# QCLogic_Rev_A_Sht7_MCU_CTRL.net
KiCad netlist of a schematic drawn in Altium Designer
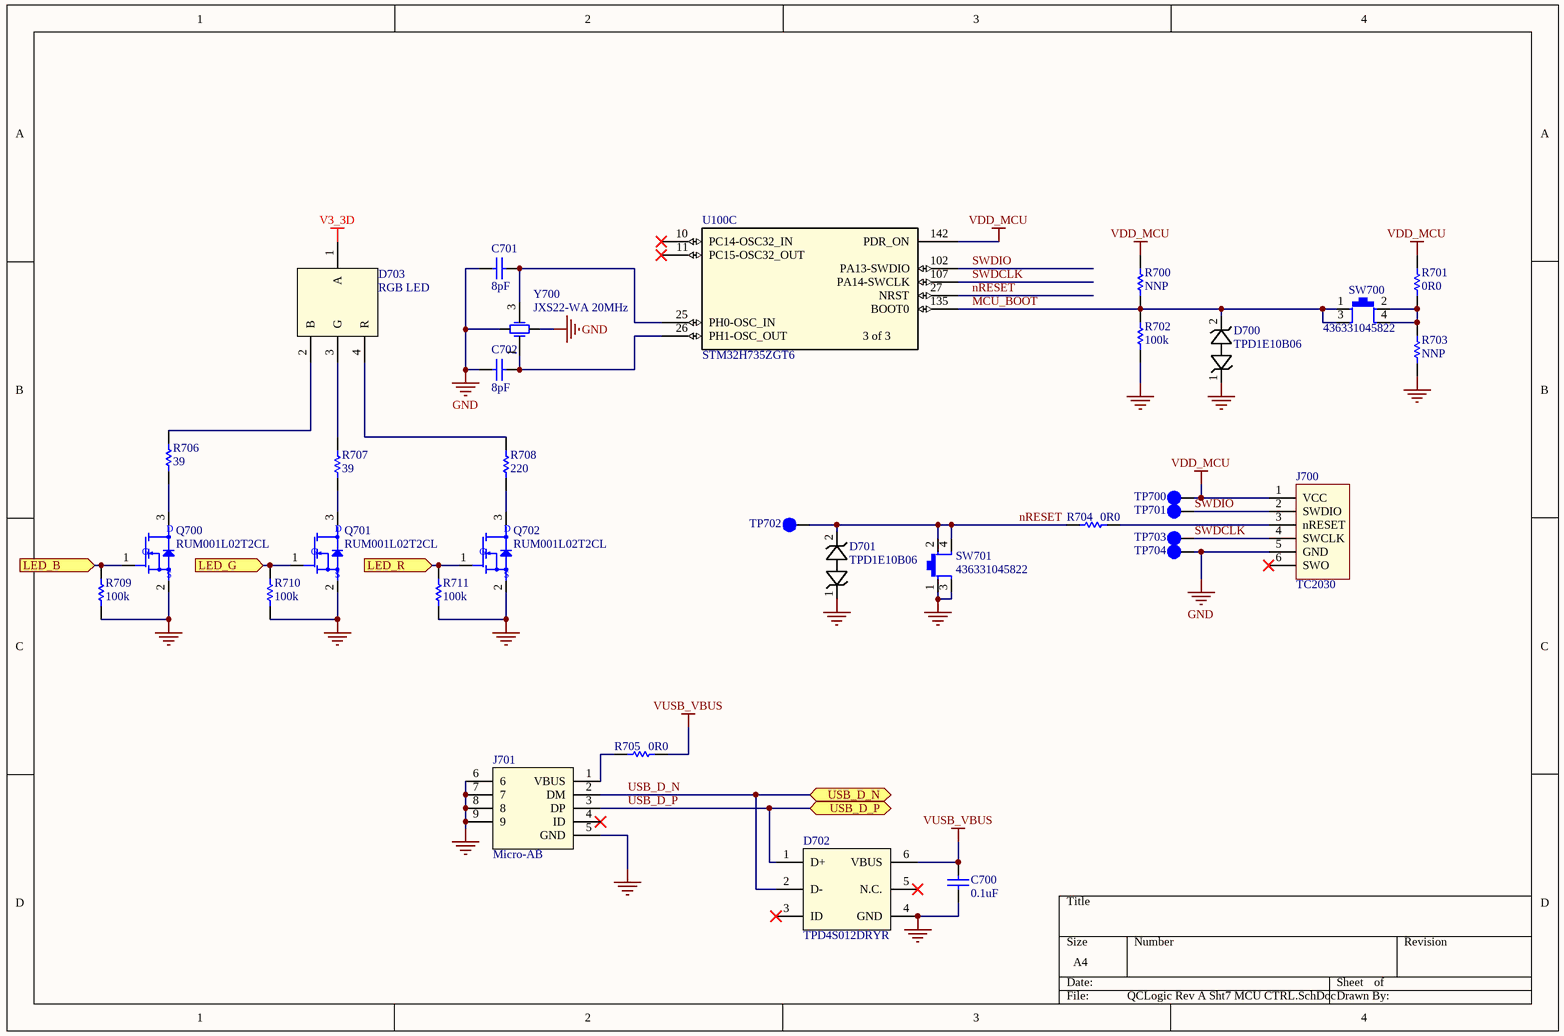
[diagram p0: QCLogic Rev A Sht7 MCU CTRL.SchDoc]

(export (version "E")
  (design (tool "Eeschema 10.0.6"))
  (components
    (comp (ref "C700")
      (value "0.1uF")
      (footprint "SMD CAP 0402")
      (description "CAP CER 0.1UF 25V X7R 0402")
      (fields (field (name "2. MANUFACTURER PART NUMBER") "CC0402KRX7R8BB104"))
      (libsource (lib "SBCLib") (part "CAP MLCC SMD"))
    )
    (comp (ref "C701")
      (value "8pF")
      (footprint "SMD CAP 0402")
      (description "CAP CER 8PF 50V C0G/NP0 0402")
      (fields (field (name "2. MANUFACTURER PART NUMBER") "CL05C080CB5NNNC"))
      (libsource (lib "SBCLib") (part "CAP MLCC SMD"))
    )
    (comp (ref "C702")
      (value "8pF")
      (footprint "SMD CAP 0402")
      (description "CAP CER 8PF 50V C0G/NP0 0402")
      (fields (field (name "2. MANUFACTURER PART NUMBER") "CL05C080CB5NNNC"))
      (libsource (lib "SBCLib") (part "CAP MLCC SMD"))
    )
    (comp (ref "D700")
      (value "TPD1E10B06")
      (footprint "DIODE 0402 2-X1SON")
      (description "DIODE TVS DIODE 5.5V 14V 2X1SON")
      (fields (field (name "2. MANUFACTURER PART NUMBER") "TPD1E10B06DPYR"))
      (libsource (lib "SBCLib") (part "DIODE TVS DIODE 5.5V 14V 2X1SON"))
    )
    (comp (ref "D701")
      (value "TPD1E10B06")
      (footprint "DIODE 0402 2-X1SON")
      (description "DIODE TVS DIODE 5.5V 14V 2X1SON")
      (fields (field (name "2. MANUFACTURER PART NUMBER") "TPD1E10B06DPYR"))
      (libsource (lib "SBCLib") (part "DIODE TVS DIODE 5.5V 14V 2X1SON"))
    )
    (comp (ref "D702")
      (value "TPD4S012DRYR")
      (footprint "SON-6 1.45x1")
      (description "DIODE TVS 4CH 5.5V 6SON")
      (libsource (lib "SBCLib") (part "DIODE TVS 4CH 5.5V 6SON"))
    )
    (comp (ref "D703")
      (value "RGB LED")
      (footprint "PLCC-4 LED ASMB-MTB0-0A3A2")
      (description "LED RGB DIFFUSED 4PLCC SMD")
      (fields (field (name "2. MANUFACTURER PART NUMBER") "ASMB-MTB0-0A3A2"))
      (libsource (lib "SBCLib") (part "LED RGB DIFFUSED 4PLCC SMD"))
    )
    (comp (ref "J700")
      (value "TC2030")
      (footprint "tag-connect-6")
      (description "TC2030 PGM PADS")
      (fields (field (name "2. MANUFACTURER PART NUMBER") "NA"))
      (libsource (lib "MasterLiiiib") (part "TC2030"))
    )
    (comp (ref "J701")
      (value "Micro-AB")
      (footprint "CONN USB MICRO_AB")
      (description "CONN RCPT USB2.0 MICRO AB SMD RA")
      (fields (field (name "2. MANUFACTURER PART NUMBER") "ZX62-AB-5PA(31)"))
      (libsource (lib "SBCLib") (part "CONN RCPT USB2.0 MICRO AB SMD RA"))
    )
    (comp (ref "Q700")
      (value "RUM001L02T2CL")
      (footprint "SOT-723")
      (description "TRANS FET N-CH 20V 0.1A SOT-723 RUM001L02T2CL")
      (libsource (lib "SBCLib") (part "TRANS FET N-CH 20V 0.1A SOT-723 RUM001L02T2CL"))
    )
    (comp (ref "Q701")
      (value "RUM001L02T2CL")
      (footprint "SOT-723")
      (description "TRANS FET N-CH 20V 0.1A SOT-723 RUM001L02T2CL")
      (libsource (lib "SBCLib") (part "TRANS FET N-CH 20V 0.1A SOT-723 RUM001L02T2CL"))
    )
    (comp (ref "Q702")
      (value "RUM001L02T2CL")
      (footprint "SOT-723")
      (description "TRANS FET N-CH 20V 0.1A SOT-723 RUM001L02T2CL")
      (libsource (lib "SBCLib") (part "TRANS FET N-CH 20V 0.1A SOT-723 RUM001L02T2CL"))
    )
    (comp (ref "R700")
      (value "NNP")
      (footprint "SMD RES 0402")
      (description "RES SMD 100K OHM 1% 1/16W 0402")
      (fields (field (name "2. MANUFACTURER PART NUMBER") "RC0402FR-07100KL"))
      (libsource (lib "SBCLib") (part "RES SMD"))
    )
    (comp (ref "R701")
      (value "0R0")
      (footprint "SMD RES 0402")
      (description "RES SMD 0 OHM JUMPER 1/16W 0402")
      (fields (field (name "2. MANUFACTURER PART NUMBER") "RC0402FR-070RL"))
      (libsource (lib "SBCLib") (part "RES SMD"))
    )
    (comp (ref "R702")
      (value "100k")
      (footprint "SMD RES 0402")
      (description "RES SMD 100K OHM 1% 1/16W 0402")
      (fields (field (name "2. MANUFACTURER PART NUMBER") "RC0402FR-07100KL"))
      (libsource (lib "SBCLib") (part "RES SMD"))
    )
    (comp (ref "R703")
      (value "NNP")
      (footprint "SMD RES 0402")
      (description "RES SMD 0 OHM JUMPER 1/16W 0402")
      (fields (field (name "2. MANUFACTURER PART NUMBER") "RC0402FR-070RL"))
      (libsource (lib "SBCLib") (part "RES SMD"))
    )
    (comp (ref "R704")
      (value "0R0")
      (footprint "SMD RES 0402")
      (description "RES SMD 0 OHM JUMPER 1/16W 0402")
      (fields (field (name "2. MANUFACTURER PART NUMBER") "RC0402FR-070RL"))
      (libsource (lib "SBCLib") (part "RES SMD"))
    )
    (comp (ref "R705")
      (value "0R0")
      (footprint "SMD RES 0402")
      (description "RES SMD 0 OHM JUMPER 1/16W 0402")
      (fields (field (name "2. MANUFACTURER PART NUMBER") "RC0402FR-070RL"))
      (libsource (lib "SBCLib") (part "RES SMD"))
    )
    (comp (ref "R706")
      (value "39")
      (footprint "SMD RES 0402")
      (description "RES SMD 39 OHM 5% 1/16W 0402")
      (fields (field (name "2. MANUFACTURER PART NUMBER") "RC0402JR-0739RL"))
      (libsource (lib "SBCLib") (part "RES SMD"))
    )
    (comp (ref "R707")
      (value "39")
      (footprint "SMD RES 0402")
      (description "RES SMD 39 OHM 5% 1/16W 0402")
      (fields (field (name "2. MANUFACTURER PART NUMBER") "RC0402JR-0739RL"))
      (libsource (lib "SBCLib") (part "RES SMD"))
    )
    (comp (ref "R708")
      (value "220")
      (footprint "SMD RES 0402")
      (description "RES SMD 220 OHM 5% 1/16W 0402")
      (fields (field (name "2. MANUFACTURER PART NUMBER") "RC0402JR-07220RL"))
      (libsource (lib "SBCLib") (part "RES SMD"))
    )
    (comp (ref "R709")
      (value "100k")
      (footprint "SMD RES 0402")
      (description "RES SMD 100K OHM 1% 1/16W 0402")
      (fields (field (name "2. MANUFACTURER PART NUMBER") "RC0402FR-07100KL"))
      (libsource (lib "SBCLib") (part "RES SMD"))
    )
    (comp (ref "R710")
      (value "100k")
      (footprint "SMD RES 0402")
      (description "RES SMD 100K OHM 1% 1/16W 0402")
      (fields (field (name "2. MANUFACTURER PART NUMBER") "RC0402FR-07100KL"))
      (libsource (lib "SBCLib") (part "RES SMD"))
    )
    (comp (ref "R711")
      (value "100k")
      (footprint "SMD RES 0402")
      (description "RES SMD 100K OHM 1% 1/16W 0402")
      (fields (field (name "2. MANUFACTURER PART NUMBER") "RC0402FR-07100KL"))
      (libsource (lib "SBCLib") (part "RES SMD"))
    )
    (comp (ref "SW700")
      (value "436331045822")
      (footprint "BUTTON 436331045822")
      (description "SWITCH R/A TACTILE SPST-NO 0.05A 12V")
      (libsource (lib "") (part "SWITCH R/A TACTILE SPST-NO 0.05A 12V_1"))
    )
    (comp (ref "SW701")
      (value "436331045822")
      (footprint "BUTTON 436331045822")
      (description "SWITCH R/A TACTILE SPST-NO 0.05A 12V")
      (libsource (lib "SBCLib") (part "SWITCH R/A TACTILE SPST-NO 0.05A 12V"))
    )
    (comp (ref "TP700")
      (value "TESTPOINT SMD")
      (footprint "TESTPOINT 1mm DIA")
      (description "TESTPOINT SMD PAD")
      (libsource (lib "SBCLib") (part "TESTPOINT PAD"))
    )
    (comp (ref "TP701")
      (value "TESTPOINT SMD")
      (footprint "TESTPOINT 1mm DIA")
      (description "TESTPOINT SMD PAD")
      (libsource (lib "SBCLib") (part "TESTPOINT PAD"))
    )
    (comp (ref "TP702")
      (value "TESTPOINT SMD")
      (footprint "TESTPOINT 1mm DIA")
      (description "TESTPOINT SMD PAD")
      (libsource (lib "SBCLib") (part "TESTPOINT PAD"))
    )
    (comp (ref "TP703")
      (value "TESTPOINT SMD")
      (footprint "TESTPOINT 1mm DIA")
      (description "TESTPOINT SMD PAD")
      (libsource (lib "SBCLib") (part "TESTPOINT PAD"))
    )
    (comp (ref "TP704")
      (value "TESTPOINT SMD")
      (footprint "TESTPOINT 1mm DIA")
      (description "TESTPOINT SMD PAD")
      (libsource (lib "SBCLib") (part "TESTPOINT PAD"))
    )
    (comp (ref "U100")
      (value "STM32H735ZGT6")
      (footprint "LQFP-144 20x20")
      (description "ARM® Cortex®-M7 STM32H7 Microcontroller IC 32-Bit 550MHz 1MB (1M x 8) FLASH 144 LQFP 20x20")
      (libsource (lib "SBCLib") (part "IC MCU STM32H735ZG Arm M7"))
    )
    (comp (ref "Y700")
      (value "JXS22-WA 20MHz")
      (footprint "XTAL JXS22-WA")
      (description "XTAL JXS22-WA 20MHz 10PF SMD")
      (fields (field (name "2. MANUFACTURER PART NUMBER") "Q 20,0-JXS22-10-10/15-T1-FU-WA-LF"))
      (libsource (lib "SBCLib") (part "XTAL JXS22-WA 20MHz 10PF SMD"))
    )
  )
  (nets
    (net (code "1") (name "/LED_B") (class "Default")
      (node (ref "Q700") (pin "1") (pinfunction "G_1") (pintype "passive"))
      (node (ref "R709") (pin "1") (pinfunction "1_1") (pintype "passive"))
    )
    (net (code "2") (name "/LED_G") (class "Default")
      (node (ref "Q701") (pin "1") (pinfunction "G_1") (pintype "passive"))
      (node (ref "R710") (pin "1") (pinfunction "1_1") (pintype "passive"))
    )
    (net (code "3") (name "/LED_R") (class "Default")
      (node (ref "Q702") (pin "1") (pinfunction "G_1") (pintype "passive"))
      (node (ref "R711") (pin "1") (pinfunction "1_1") (pintype "passive"))
    )
    (net (code "4") (name "/MCU_BOOT") (class "Default")
      (node (ref "D700") (pin "2") (pinfunction "2_2") (pintype "passive"))
      (node (ref "R700") (pin "2") (pinfunction "2_2") (pintype "passive"))
      (node (ref "R702") (pin "1") (pinfunction "1_1") (pintype "passive"))
      (node (ref "SW700") (pin "1") (pinfunction "1_1") (pintype "passive"))
      (node (ref "SW700") (pin "3") (pinfunction "3_3") (pintype "passive"))
      (node (ref "U100") (pin "135") (pinfunction "BOOT0_135") (pintype "bidirectional"))
    )
    (net (code "5") (name "/SWDCLK") (class "Default")
      (node (ref "J700") (pin "4") (pinfunction "SWCLK_4") (pintype "passive"))
      (node (ref "TP703") (pin "1") (pinfunction "1_1") (pintype "passive"))
      (node (ref "U100") (pin "107") (pinfunction "PA14-SWCLK_107") (pintype "bidirectional"))
    )
    (net (code "6") (name "/SWDIO") (class "Default")
      (node (ref "J700") (pin "2") (pinfunction "SWDIO_2") (pintype "passive"))
      (node (ref "TP701") (pin "1") (pinfunction "1_1") (pintype "passive"))
      (node (ref "U100") (pin "102") (pinfunction "PA13-SWDIO_102") (pintype "bidirectional"))
    )
    (net (code "7") (name "/USB_D_N") (class "Default")
      (node (ref "D702") (pin "2") (pinfunction "D-_2") (pintype "passive"))
      (node (ref "J701") (pin "2") (pinfunction "DM_2") (pintype "passive"))
    )
    (net (code "8") (name "/USB_D_P") (class "Default")
      (node (ref "D702") (pin "1") (pinfunction "D+_1") (pintype "passive"))
      (node (ref "J701") (pin "3") (pinfunction "DP_3") (pintype "passive"))
    )
    (net (code "9") (name "/nRESET") (class "Default")
      (node (ref "D701") (pin "2") (pinfunction "2_2") (pintype "passive"))
      (node (ref "R704") (pin "1") (pinfunction "1_1") (pintype "passive"))
      (node (ref "SW701") (pin "2") (pinfunction "2_2") (pintype "passive"))
      (node (ref "SW701") (pin "4") (pinfunction "4_4") (pintype "passive"))
      (node (ref "TP702") (pin "1") (pinfunction "1_1") (pintype "passive"))
      (node (ref "U100") (pin "27") (pinfunction "NRST_27") (pintype "bidirectional"))
    )
    (net (code "10") (name "GND") (class "Default")
      (node (ref "C700") (pin "1") (pinfunction "1_1") (pintype "passive"))
      (node (ref "C701") (pin "2") (pinfunction "2_2") (pintype "passive"))
      (node (ref "C702") (pin "2") (pinfunction "2_2") (pintype "passive"))
      (node (ref "D700") (pin "1") (pinfunction "1_1") (pintype "passive"))
      (node (ref "D701") (pin "1") (pinfunction "1_1") (pintype "passive"))
      (node (ref "D702") (pin "4") (pinfunction "GND_4") (pintype "power_in"))
      (node (ref "J700") (pin "5") (pinfunction "GND_5") (pintype "passive"))
      (node (ref "J701") (pin "5") (pinfunction "GND_5") (pintype "passive"))
      (node (ref "J701") (pin "6") (pinfunction "6_6") (pintype "passive"))
      (node (ref "J701") (pin "7") (pinfunction "7_7") (pintype "passive"))
      (node (ref "J701") (pin "8") (pinfunction "8_8") (pintype "passive"))
      (node (ref "J701") (pin "9") (pinfunction "9_9") (pintype "passive"))
      (node (ref "Q700") (pin "2") (pinfunction "2_2") (pintype "passive"))
      (node (ref "Q701") (pin "2") (pinfunction "2_2") (pintype "passive"))
      (node (ref "Q702") (pin "2") (pinfunction "2_2") (pintype "passive"))
      (node (ref "R702") (pin "2") (pinfunction "2_2") (pintype "passive"))
      (node (ref "R703") (pin "2") (pinfunction "2_2") (pintype "passive"))
      (node (ref "R709") (pin "2") (pinfunction "2_2") (pintype "passive"))
      (node (ref "R710") (pin "2") (pinfunction "2_2") (pintype "passive"))
      (node (ref "R711") (pin "2") (pinfunction "2_2") (pintype "passive"))
      (node (ref "SW701") (pin "1") (pinfunction "1_1") (pintype "passive"))
      (node (ref "SW701") (pin "3") (pinfunction "3_3") (pintype "passive"))
      (node (ref "TP704") (pin "1") (pinfunction "1_1") (pintype "passive"))
      (node (ref "Y700") (pin "2") (pinfunction "2_2") (pintype "passive"))
      (node (ref "Y700") (pin "4") (pinfunction "4_4") (pintype "passive"))
    )
    (net (code "11") (name "Net-(D703-B)") (class "Default")
      (node (ref "D703") (pin "2") (pinfunction "B_2") (pintype "passive"))
      (node (ref "R706") (pin "2") (pinfunction "2_2") (pintype "passive"))
    )
    (net (code "12") (name "Net-(D703-G)") (class "Default")
      (node (ref "D703") (pin "3") (pinfunction "G_3") (pintype "passive"))
      (node (ref "R707") (pin "2") (pinfunction "2_2") (pintype "passive"))
    )
    (net (code "13") (name "Net-(D703-R)") (class "Default")
      (node (ref "D703") (pin "4") (pinfunction "R_4") (pintype "passive"))
      (node (ref "R708") (pin "2") (pinfunction "2_2") (pintype "passive"))
    )
    (net (code "14") (name "Net-(J700-nRESET)") (class "Default")
      (node (ref "J700") (pin "3") (pinfunction "nRESET_3") (pintype "passive"))
      (node (ref "R704") (pin "2") (pinfunction "2_2") (pintype "passive"))
    )
    (net (code "15") (name "Net-(J701-VBUS)") (class "Default")
      (node (ref "J701") (pin "1") (pinfunction "VBUS_1") (pintype "passive"))
      (node (ref "R705") (pin "1") (pinfunction "1_1") (pintype "passive"))
    )
    (net (code "16") (name "Net-(Q700-Pad3)") (class "Default")
      (node (ref "Q700") (pin "3") (pinfunction "3_3") (pintype "passive"))
      (node (ref "R706") (pin "1") (pinfunction "1_1") (pintype "passive"))
    )
    (net (code "17") (name "Net-(Q701-Pad3)") (class "Default")
      (node (ref "Q701") (pin "3") (pinfunction "3_3") (pintype "passive"))
      (node (ref "R707") (pin "1") (pinfunction "1_1") (pintype "passive"))
    )
    (net (code "18") (name "Net-(Q702-Pad3)") (class "Default")
      (node (ref "Q702") (pin "3") (pinfunction "3_3") (pintype "passive"))
      (node (ref "R708") (pin "1") (pinfunction "1_1") (pintype "passive"))
    )
    (net (code "19") (name "Net-(R701-Pad2)") (class "Default")
      (node (ref "R701") (pin "2") (pinfunction "2_2") (pintype "passive"))
      (node (ref "R703") (pin "1") (pinfunction "1_1") (pintype "passive"))
      (node (ref "SW700") (pin "2") (pinfunction "2_2") (pintype "passive"))
      (node (ref "SW700") (pin "4") (pinfunction "4_4") (pintype "passive"))
    )
    (net (code "20") (name "Net-(U100C-PH0-OSC_IN)") (class "Default")
      (node (ref "C701") (pin "1") (pinfunction "1_1") (pintype "passive"))
      (node (ref "U100") (pin "25") (pinfunction "PH0-OSC_IN_25") (pintype "bidirectional"))
      (node (ref "Y700") (pin "3") (pinfunction "3_3") (pintype "passive"))
    )
    (net (code "21") (name "Net-(U100C-PH1-OSC_OUT)") (class "Default")
      (node (ref "C702") (pin "1") (pinfunction "1_1") (pintype "passive"))
      (node (ref "U100") (pin "26") (pinfunction "PH1-OSC_OUT_26") (pintype "bidirectional"))
      (node (ref "Y700") (pin "1") (pinfunction "1_1") (pintype "passive"))
    )
    (net (code "22") (name "V3_3D") (class "Default")
      (node (ref "D703") (pin "1") (pinfunction "A_1") (pintype "passive"))
    )
    (net (code "23") (name "VDD_MCU") (class "Default")
      (node (ref "J700") (pin "1") (pinfunction "VCC_1") (pintype "passive"))
      (node (ref "R700") (pin "1") (pinfunction "1_1") (pintype "passive"))
      (node (ref "R701") (pin "1") (pinfunction "1_1") (pintype "passive"))
      (node (ref "TP700") (pin "1") (pinfunction "1_1") (pintype "passive"))
      (node (ref "U100") (pin "142") (pinfunction "PDR_ON_142") (pintype "passive"))
    )
    (net (code "24") (name "VUSB_VBUS") (class "Default")
      (node (ref "C700") (pin "2") (pinfunction "2_2") (pintype "passive"))
      (node (ref "D702") (pin "6") (pinfunction "VBUS_6") (pintype "passive"))
      (node (ref "R705") (pin "2") (pinfunction "2_2") (pintype "passive"))
    )
    (net (code "25") (name "unconnected-(D702-ID-Pad3)") (class "Default")
      (node (ref "D702") (pin "3") (pinfunction "ID_3") (pintype "passive+no_connect"))
    )
    (net (code "26") (name "unconnected-(D702-N.C.-Pad5)") (class "Default")
      (node (ref "D702") (pin "5") (pinfunction "N.C._5") (pintype "passive+no_connect"))
    )
    (net (code "27") (name "unconnected-(J700-SWO-Pad6)") (class "Default")
      (node (ref "J700") (pin "6") (pinfunction "SWO_6") (pintype "passive+no_connect"))
    )
    (net (code "28") (name "unconnected-(J701-ID-Pad4)") (class "Default")
      (node (ref "J701") (pin "4") (pinfunction "ID_4") (pintype "passive+no_connect"))
    )
    (net (code "29") (name "unconnected-(U100C-PC14-OSC32_IN-Pad10)") (class "Default")
      (node (ref "U100") (pin "10") (pinfunction "PC14-OSC32_IN_10") (pintype "bidirectional+no_connect"))
    )
    (net (code "30") (name "unconnected-(U100C-PC15-OSC32_OUT-Pad11)") (class "Default")
      (node (ref "U100") (pin "11") (pinfunction "PC15-OSC32_OUT_11") (pintype "bidirectional+no_connect"))
    )
  )
)
